# Sheet_Digital_Input_and_Relay.net
KiCad netlist of a schematic drawn in Altium Designer
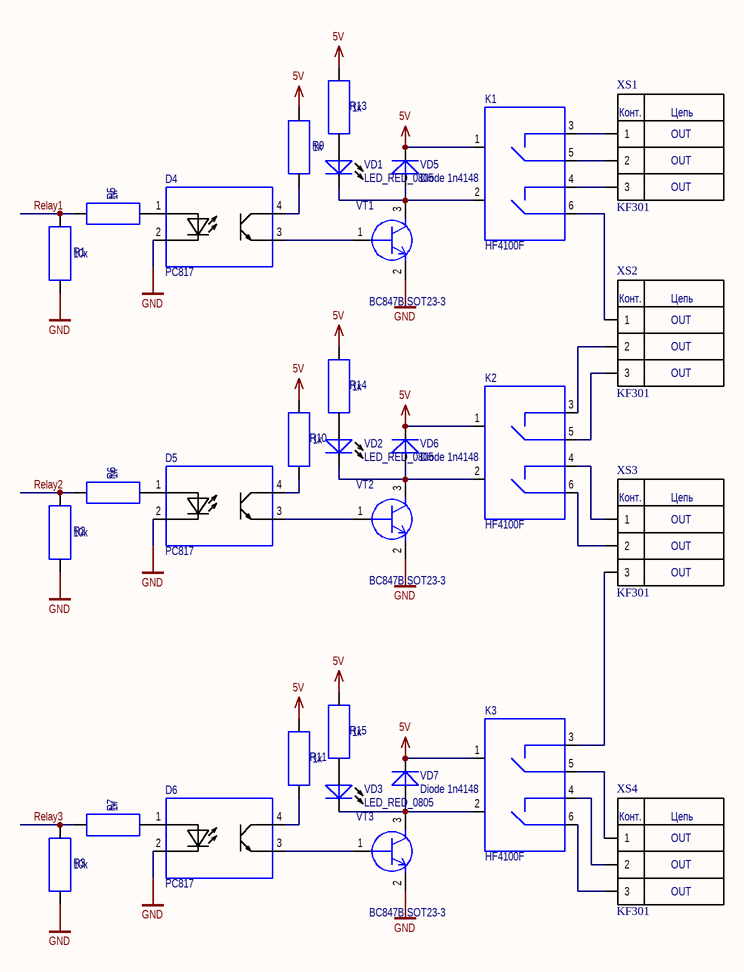
[diagram p0: Sheet_Digital_Input_and_Relay.SchDoc]

(export (version "E")
  (design (tool "Eeschema 10.0.6"))
  (components
    (comp (ref "D4")
      (value "PC817")
      (footprint "DIP-4")
      (libsource (lib "Schlib_PortalWashDD") (part "PC817"))
    )
    (comp (ref "D5")
      (value "PC817")
      (footprint "DIP-4")
      (libsource (lib "Schlib_PortalWashDD") (part "PC817"))
    )
    (comp (ref "D6")
      (value "PC817")
      (footprint "DIP-4")
      (libsource (lib "Schlib_PortalWashDD") (part "PC817"))
    )
    (comp (ref "K1")
      (value "HF4100F")
      (footprint "PcbLib_Smart_Switchboard:HK4100F")
      (libsource (lib "Schlib_Smart_Switchboard") (part "HF4100F"))
    )
    (comp (ref "K2")
      (value "HF4100F")
      (footprint "PcbLib_Smart_Switchboard:HK4100F")
      (libsource (lib "Schlib_Smart_Switchboard") (part "HF4100F"))
    )
    (comp (ref "K3")
      (value "HF4100F")
      (footprint "PcbLib_Smart_Switchboard:HK4100F")
      (libsource (lib "Schlib_Smart_Switchboard") (part "HF4100F"))
    )
    (comp (ref "R1")
      (value "10к")
      (footprint "R0603")
      (fields
        (field (name "TOLERANCE") "± 1% - М")
        (field (name "POWER") "0,1 Вт")
        (field (name "Comment") "Resistor")
      )
      (libsource (lib "Schlib_Smart_Switchboard") (part "ОСМ Р1-12 -0,1- 10 кОм ± 5%"))
    )
    (comp (ref "R2")
      (value "10к")
      (footprint "R0603")
      (fields
        (field (name "TOLERANCE") "± 1% - М")
        (field (name "POWER") "0,1 Вт")
        (field (name "Comment") "Resistor")
      )
      (libsource (lib "Schlib_Smart_Switchboard") (part "ОСМ Р1-12 -0,1- 10 кОм ± 5%"))
    )
    (comp (ref "R3")
      (value "10к")
      (footprint "R0603")
      (fields
        (field (name "TOLERANCE") "± 1% - М")
        (field (name "POWER") "0,1 Вт")
        (field (name "Comment") "Resistor")
      )
      (libsource (lib "Schlib_Smart_Switchboard") (part "ОСМ Р1-12 -0,1- 10 кОм ± 5%"))
    )
    (comp (ref "R5")
      (value "1к")
      (footprint "R0603")
      (fields
        (field (name "TOLERANCE") "± 1% - М")
        (field (name "POWER") "0,1 Вт")
        (field (name "Comment") "Resistor")
      )
      (libsource (lib "Schlib_PortalWashDD") (part "ОСМ Р1-12 -0,1- 1 кОм ± 5%"))
    )
    (comp (ref "R6")
      (value "1к")
      (footprint "R0603")
      (fields
        (field (name "TOLERANCE") "± 1% - М")
        (field (name "POWER") "0,1 Вт")
        (field (name "Comment") "Resistor")
      )
      (libsource (lib "Schlib_PortalWashDD") (part "ОСМ Р1-12 -0,1- 1 кОм ± 5%"))
    )
    (comp (ref "R7")
      (value "1к")
      (footprint "R0603")
      (fields
        (field (name "TOLERANCE") "± 1% - М")
        (field (name "POWER") "0,1 Вт")
        (field (name "Comment") "Resistor")
      )
      (libsource (lib "Schlib_PortalWashDD") (part "ОСМ Р1-12 -0,1- 1 кОм ± 5%"))
    )
    (comp (ref "R9")
      (value "1к")
      (footprint "R0603")
      (fields
        (field (name "TOLERANCE") "± 1% - М")
        (field (name "POWER") "0,1 Вт")
        (field (name "Comment") "Resistor")
      )
      (libsource (lib "Schlib_PortalWashDD") (part "ОСМ Р1-12 -0,1- 1 кОм ± 5%"))
    )
    (comp (ref "R10")
      (value "1к")
      (footprint "R0603")
      (fields
        (field (name "TOLERANCE") "± 1% - М")
        (field (name "POWER") "0,1 Вт")
        (field (name "Comment") "Resistor")
      )
      (libsource (lib "Schlib_PortalWashDD") (part "ОСМ Р1-12 -0,1- 1 кОм ± 5%"))
    )
    (comp (ref "R11")
      (value "1к")
      (footprint "R0603")
      (fields
        (field (name "TOLERANCE") "± 1% - М")
        (field (name "POWER") "0,1 Вт")
        (field (name "Comment") "Resistor")
      )
      (libsource (lib "Schlib_PortalWashDD") (part "ОСМ Р1-12 -0,1- 1 кОм ± 5%"))
    )
    (comp (ref "R13")
      (value "1к")
      (footprint "R0603")
      (fields
        (field (name "TOLERANCE") "± 1% - М")
        (field (name "POWER") "0,1 Вт")
        (field (name "Comment") "Resistor")
      )
      (libsource (lib "Schlib_PortalWashDD") (part "ОСМ Р1-12 -0,1- 1 кОм ± 5%"))
    )
    (comp (ref "R14")
      (value "1к")
      (footprint "R0603")
      (fields
        (field (name "TOLERANCE") "± 1% - М")
        (field (name "POWER") "0,1 Вт")
        (field (name "Comment") "Resistor")
      )
      (libsource (lib "Schlib_PortalWashDD") (part "ОСМ Р1-12 -0,1- 1 кОм ± 5%"))
    )
    (comp (ref "R15")
      (value "1к")
      (footprint "R0603")
      (fields
        (field (name "TOLERANCE") "± 1% - М")
        (field (name "POWER") "0,1 Вт")
        (field (name "Comment") "Resistor")
      )
      (libsource (lib "Schlib_PortalWashDD") (part "ОСМ Р1-12 -0,1- 1 кОм ± 5%"))
    )
    (comp (ref "VD1")
      (value "LED_RED_0805")
      (footprint "VD0805")
      (libsource (lib "Schlib_PortalWashDD") (part "LED_RED_0805"))
    )
    (comp (ref "VD2")
      (value "LED_RED_0805")
      (footprint "VD0805")
      (libsource (lib "Schlib_PortalWashDD") (part "LED_RED_0805"))
    )
    (comp (ref "VD3")
      (value "LED_RED_0805")
      (footprint "VD0805")
      (libsource (lib "Schlib_PortalWashDD") (part "LED_RED_0805"))
    )
    (comp (ref "VD5")
      (value "Diode 1n4148")
      (footprint "SOD323")
      (libsource (lib "Schlib_PortalWashDD") (part "Diode 1n4148"))
    )
    (comp (ref "VD6")
      (value "Diode 1n4148")
      (footprint "SOD323")
      (libsource (lib "Schlib_PortalWashDD") (part "Diode 1n4148"))
    )
    (comp (ref "VD7")
      (value "Diode 1n4148")
      (footprint "SOD323")
      (libsource (lib "Schlib_PortalWashDD") (part "Diode 1n4148"))
    )
    (comp (ref "VT1")
      (value "BC847B SOT23-3")
      (footprint "INF-SOT23_M")
      (description "NPN Transistor")
      (libsource (lib "Schlib_PortalWashDD") (part "BC847B SOT23-3"))
    )
    (comp (ref "VT2")
      (value "BC847B SOT23-3")
      (footprint "INF-SOT23_M")
      (description "NPN Transistor")
      (libsource (lib "Schlib_PortalWashDD") (part "BC847B SOT23-3"))
    )
    (comp (ref "VT3")
      (value "BC847B SOT23-3")
      (footprint "INF-SOT23_M")
      (description "NPN Transistor")
      (libsource (lib "Schlib_PortalWashDD") (part "BC847B SOT23-3"))
    )
    (comp (ref "XS1")
      (value "KF301")
      (footprint "KF301-5.08-3P")
      (libsource (lib "Schlib_PortalWashDD") (part "KF301"))
    )
    (comp (ref "XS2")
      (value "KF301")
      (footprint "KF301-5.08-3P")
      (libsource (lib "Schlib_PortalWashDD") (part "KF301"))
    )
    (comp (ref "XS3")
      (value "KF301")
      (footprint "KF301-5.08-3P")
      (libsource (lib "Schlib_PortalWashDD") (part "KF301"))
    )
    (comp (ref "XS4")
      (value "KF301")
      (footprint "KF301-5.08-3P")
      (libsource (lib "Schlib_PortalWashDD") (part "KF301"))
    )
  )
  (nets
    (net (code "1") (name "/Relay1") (class "Default")
      (node (ref "R1") (pin "1") (pinfunction "1_1") (pintype "passive"))
      (node (ref "R5") (pin "1") (pinfunction "1_1") (pintype "passive"))
    )
    (net (code "2") (name "/Relay2") (class "Default")
      (node (ref "R2") (pin "1") (pinfunction "1_1") (pintype "passive"))
      (node (ref "R6") (pin "1") (pinfunction "1_1") (pintype "passive"))
    )
    (net (code "3") (name "/Relay3") (class "Default")
      (node (ref "R3") (pin "1") (pinfunction "1_1") (pintype "passive"))
      (node (ref "R7") (pin "1") (pinfunction "1_1") (pintype "passive"))
    )
    (net (code "4") (name "5V") (class "Default")
      (node (ref "K1") (pin "1") (pinfunction "1_1") (pintype "passive"))
      (node (ref "K2") (pin "1") (pinfunction "1_1") (pintype "passive"))
      (node (ref "K3") (pin "1") (pinfunction "1_1") (pintype "passive"))
      (node (ref "R10") (pin "1") (pinfunction "1_1") (pintype "passive"))
      (node (ref "R11") (pin "1") (pinfunction "1_1") (pintype "passive"))
      (node (ref "R13") (pin "1") (pinfunction "1_1") (pintype "passive"))
      (node (ref "R14") (pin "1") (pinfunction "1_1") (pintype "passive"))
      (node (ref "R15") (pin "1") (pinfunction "1_1") (pintype "passive"))
      (node (ref "R9") (pin "1") (pinfunction "1_1") (pintype "passive"))
      (node (ref "VD5") (pin "2") (pinfunction "2_2") (pintype "passive"))
      (node (ref "VD6") (pin "2") (pinfunction "2_2") (pintype "passive"))
      (node (ref "VD7") (pin "2") (pinfunction "2_2") (pintype "passive"))
    )
    (net (code "5") (name "GND") (class "Default")
      (node (ref "D4") (pin "2") (pinfunction "Cathode_2") (pintype "passive"))
      (node (ref "D5") (pin "2") (pinfunction "Cathode_2") (pintype "passive"))
      (node (ref "D6") (pin "2") (pinfunction "Cathode_2") (pintype "passive"))
      (node (ref "R1") (pin "2") (pinfunction "2_2") (pintype "passive"))
      (node (ref "R2") (pin "2") (pinfunction "2_2") (pintype "passive"))
      (node (ref "R3") (pin "2") (pinfunction "2_2") (pintype "passive"))
      (node (ref "VT1") (pin "2") (pinfunction "E_2") (pintype "passive"))
      (node (ref "VT2") (pin "2") (pinfunction "E_2") (pintype "passive"))
      (node (ref "VT3") (pin "2") (pinfunction "E_2") (pintype "passive"))
    )
    (net (code "6") (name "Net-(D4-Anode)") (class "Default")
      (node (ref "D4") (pin "1") (pinfunction "Anode_1") (pintype "passive"))
      (node (ref "R5") (pin "2") (pinfunction "2_2") (pintype "passive"))
    )
    (net (code "7") (name "Net-(D4-Collector)") (class "Default")
      (node (ref "D4") (pin "4") (pinfunction "Collector_4") (pintype "passive"))
      (node (ref "R9") (pin "2") (pinfunction "2_2") (pintype "passive"))
    )
    (net (code "8") (name "Net-(D4-Emitter)") (class "Default")
      (node (ref "D4") (pin "3") (pinfunction "Emitter_3") (pintype "passive"))
      (node (ref "VT1") (pin "1") (pinfunction "B_1") (pintype "passive"))
    )
    (net (code "9") (name "Net-(D5-Anode)") (class "Default")
      (node (ref "D5") (pin "1") (pinfunction "Anode_1") (pintype "passive"))
      (node (ref "R6") (pin "2") (pinfunction "2_2") (pintype "passive"))
    )
    (net (code "10") (name "Net-(D5-Collector)") (class "Default")
      (node (ref "D5") (pin "4") (pinfunction "Collector_4") (pintype "passive"))
      (node (ref "R10") (pin "2") (pinfunction "2_2") (pintype "passive"))
    )
    (net (code "11") (name "Net-(D5-Emitter)") (class "Default")
      (node (ref "D5") (pin "3") (pinfunction "Emitter_3") (pintype "passive"))
      (node (ref "VT2") (pin "1") (pinfunction "B_1") (pintype "passive"))
    )
    (net (code "12") (name "Net-(D6-Anode)") (class "Default")
      (node (ref "D6") (pin "1") (pinfunction "Anode_1") (pintype "passive"))
      (node (ref "R7") (pin "2") (pinfunction "2_2") (pintype "passive"))
    )
    (net (code "13") (name "Net-(D6-Collector)") (class "Default")
      (node (ref "D6") (pin "4") (pinfunction "Collector_4") (pintype "passive"))
      (node (ref "R11") (pin "2") (pinfunction "2_2") (pintype "passive"))
    )
    (net (code "14") (name "Net-(D6-Emitter)") (class "Default")
      (node (ref "D6") (pin "3") (pinfunction "Emitter_3") (pintype "passive"))
      (node (ref "VT3") (pin "1") (pinfunction "B_1") (pintype "passive"))
    )
    (net (code "15") (name "Net-(K1-Pad3)") (class "Default")
      (node (ref "K1") (pin "3") (pinfunction "3_3") (pintype "passive"))
      (node (ref "XS1") (pin "1") (pinfunction "1_1") (pintype "passive"))
    )
    (net (code "16") (name "Net-(K1-Pad4)") (class "Default")
      (node (ref "K1") (pin "4") (pinfunction "4_4") (pintype "passive"))
      (node (ref "XS1") (pin "3") (pinfunction "3_3") (pintype "passive"))
    )
    (net (code "17") (name "Net-(K1-Pad5)") (class "Default")
      (node (ref "K1") (pin "5") (pinfunction "5_5") (pintype "passive"))
      (node (ref "XS1") (pin "2") (pinfunction "2_2") (pintype "passive"))
    )
    (net (code "18") (name "Net-(K1-Pad6)") (class "Default")
      (node (ref "K1") (pin "6") (pinfunction "6_6") (pintype "passive"))
      (node (ref "XS2") (pin "1") (pinfunction "1_1") (pintype "passive"))
    )
    (net (code "19") (name "Net-(K2-Pad3)") (class "Default")
      (node (ref "K2") (pin "3") (pinfunction "3_3") (pintype "passive"))
      (node (ref "XS2") (pin "2") (pinfunction "2_2") (pintype "passive"))
    )
    (net (code "20") (name "Net-(K2-Pad4)") (class "Default")
      (node (ref "K2") (pin "4") (pinfunction "4_4") (pintype "passive"))
      (node (ref "XS3") (pin "1") (pinfunction "1_1") (pintype "passive"))
    )
    (net (code "21") (name "Net-(K2-Pad5)") (class "Default")
      (node (ref "K2") (pin "5") (pinfunction "5_5") (pintype "passive"))
      (node (ref "XS2") (pin "3") (pinfunction "3_3") (pintype "passive"))
    )
    (net (code "22") (name "Net-(K2-Pad6)") (class "Default")
      (node (ref "K2") (pin "6") (pinfunction "6_6") (pintype "passive"))
      (node (ref "XS3") (pin "2") (pinfunction "2_2") (pintype "passive"))
    )
    (net (code "23") (name "Net-(K3-Pad3)") (class "Default")
      (node (ref "K3") (pin "3") (pinfunction "3_3") (pintype "passive"))
      (node (ref "XS3") (pin "3") (pinfunction "3_3") (pintype "passive"))
    )
    (net (code "24") (name "Net-(K3-Pad4)") (class "Default")
      (node (ref "K3") (pin "4") (pinfunction "4_4") (pintype "passive"))
      (node (ref "XS4") (pin "2") (pinfunction "2_2") (pintype "passive"))
    )
    (net (code "25") (name "Net-(K3-Pad5)") (class "Default")
      (node (ref "K3") (pin "5") (pinfunction "5_5") (pintype "passive"))
      (node (ref "XS4") (pin "1") (pinfunction "1_1") (pintype "passive"))
    )
    (net (code "26") (name "Net-(K3-Pad6)") (class "Default")
      (node (ref "K3") (pin "6") (pinfunction "6_6") (pintype "passive"))
      (node (ref "XS4") (pin "3") (pinfunction "3_3") (pintype "passive"))
    )
    (net (code "27") (name "Net-(R13-Pad2)") (class "Default")
      (node (ref "R13") (pin "2") (pinfunction "2_2") (pintype "passive"))
      (node (ref "VD1") (pin "1") (pinfunction "1_1") (pintype "passive"))
    )
    (net (code "28") (name "Net-(R14-Pad2)") (class "Default")
      (node (ref "R14") (pin "2") (pinfunction "2_2") (pintype "passive"))
      (node (ref "VD2") (pin "1") (pinfunction "1_1") (pintype "passive"))
    )
    (net (code "29") (name "Net-(R15-Pad2)") (class "Default")
      (node (ref "R15") (pin "2") (pinfunction "2_2") (pintype "passive"))
      (node (ref "VD3") (pin "1") (pinfunction "1_1") (pintype "passive"))
    )
    (net (code "30") (name "Net-(VT1-K)") (class "Default")
      (node (ref "K1") (pin "2") (pinfunction "2_2") (pintype "passive"))
      (node (ref "VD1") (pin "2") (pinfunction "2_2") (pintype "passive"))
      (node (ref "VD5") (pin "1") (pinfunction "1_1") (pintype "passive"))
      (node (ref "VT1") (pin "3") (pinfunction "K_3") (pintype "passive"))
    )
    (net (code "31") (name "Net-(VT2-K)") (class "Default")
      (node (ref "K2") (pin "2") (pinfunction "2_2") (pintype "passive"))
      (node (ref "VD2") (pin "2") (pinfunction "2_2") (pintype "passive"))
      (node (ref "VD6") (pin "1") (pinfunction "1_1") (pintype "passive"))
      (node (ref "VT2") (pin "3") (pinfunction "K_3") (pintype "passive"))
    )
    (net (code "32") (name "Net-(VT3-K)") (class "Default")
      (node (ref "K3") (pin "2") (pinfunction "2_2") (pintype "passive"))
      (node (ref "VD3") (pin "2") (pinfunction "2_2") (pintype "passive"))
      (node (ref "VD7") (pin "1") (pinfunction "1_1") (pintype "passive"))
      (node (ref "VT3") (pin "3") (pinfunction "K_3") (pintype "passive"))
    )
  )
)
